# ArmDebuger_7-7_-CPLD.net
KiCad netlist of a schematic drawn in Altium Designer
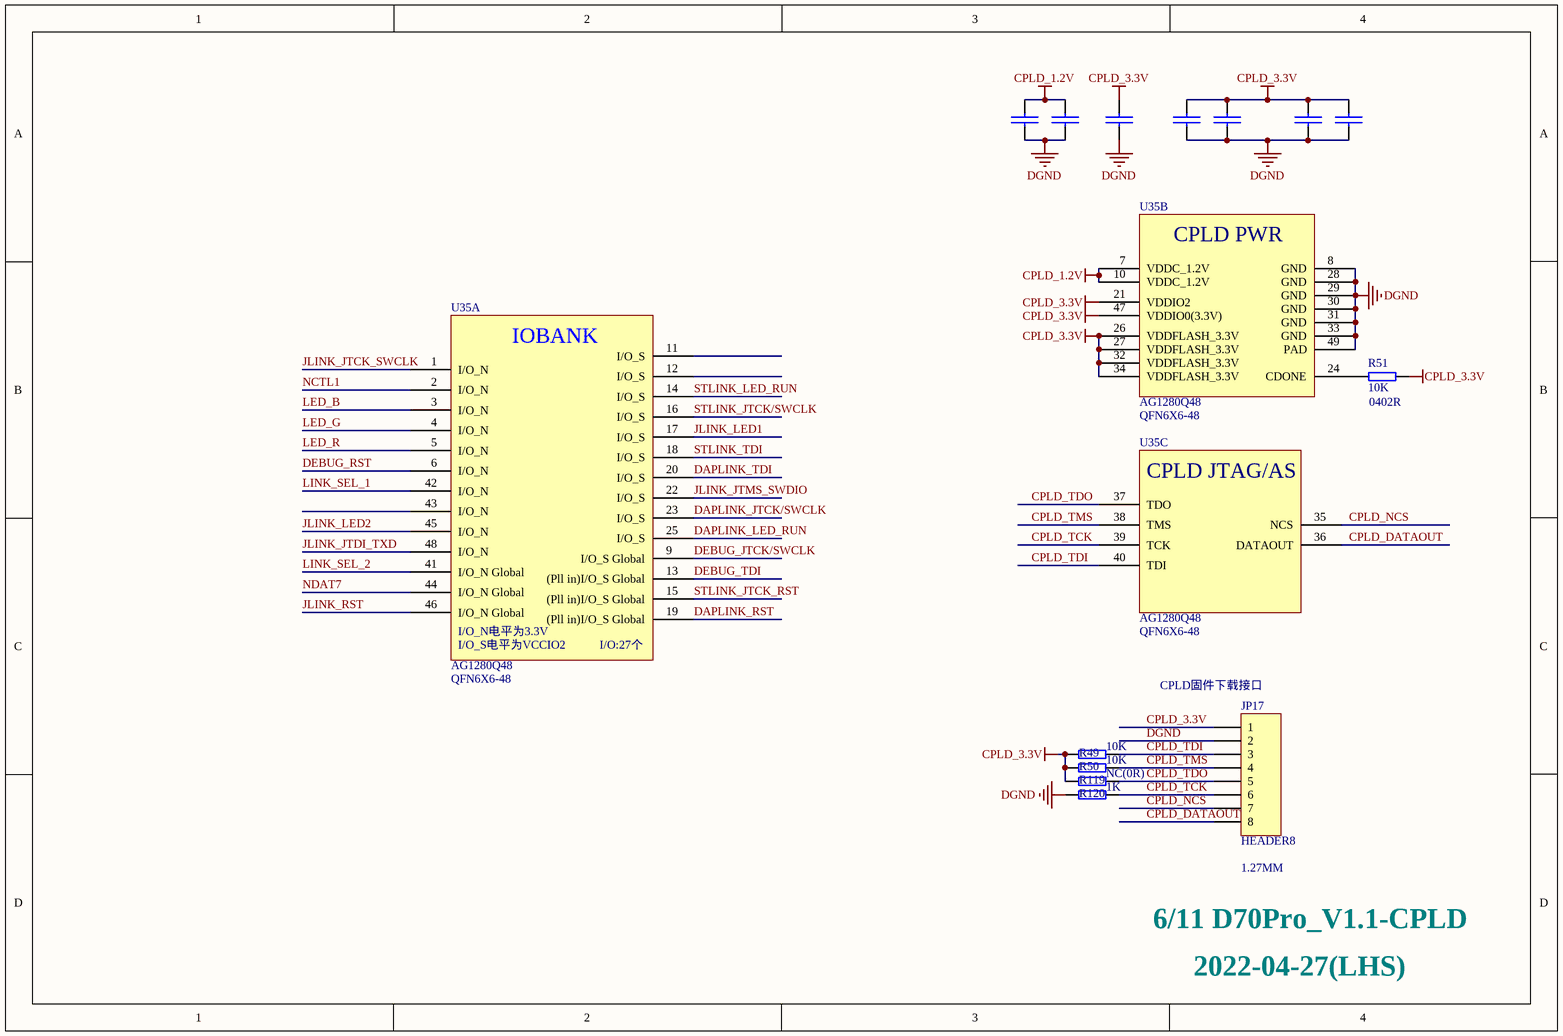
[diagram p0: ArmDebuger(7-7)-CPLD.SchDoc]

(export (version "E")
  (design (tool "Eeschema 10.0.6"))
  (components
    (comp (ref "C105") (value "104/X7R/16V") (footprint "0402C-SMD-M") (libsource (lib "*") (part "CAP")))
    (comp (ref "C172") (value "104/X7R/16V") (footprint "0402C-SMD-M") (libsource (lib "*") (part "CAP")))
    (comp (ref "C223") (value "104/X7R/16V") (footprint "0402C-SMD-M") (libsource (lib "*") (part "CAP")))
    (comp (ref "C224") (value "104/X7R/16V") (footprint "0402C-SMD-M") (libsource (lib "*") (part "CAP")))
    (comp (ref "C227") (value "104/X7R/16V") (footprint "0402C-SMD-M") (libsource (lib "*") (part "CAP")))
    (comp (ref "C228") (value "104/X7R/16V") (footprint "0402C-SMD-M") (libsource (lib "*") (part "CAP")))
    (comp (ref "C229") (value "104/X7R/16V") (footprint "0402C-SMD-M") (libsource (lib "*") (part "CAP")))
    (comp (ref "JP17")
      (value "HEADER8")
      (footprint "HEADER4x2-1.27mm")
      (fields (field (name "FP") "1.27MM"))
      (libsource (lib "conm") (part "HEADER8"))
    )
    (comp (ref "R49")
      (value "10K")
      (footprint "0402R-SMD-M")
      (libsource (lib "altium-import") (part "root_2_RES_"))
    )
    (comp (ref "R50")
      (value "10K")
      (footprint "0402R-SMD-M")
      (libsource (lib "altium-import") (part "root_2_RES_"))
    )
    (comp (ref "R51")
      (value "10K")
      (footprint "0402R-SMD-M")
      (fields (field (name "FP") "0402R"))
      (libsource (lib "altium-import") (part "root_2_RES_"))
    )
    (comp (ref "R119")
      (value "NC(0R)")
      (footprint "0402R-SMD-M")
      (libsource (lib "altium-import") (part "root_2_RES_"))
    )
    (comp (ref "R120")
      (value "1K")
      (footprint "0402R-SMD-M")
      (libsource (lib "altium-import") (part "root_2_RES_"))
    )
    (comp (ref "U35")
      (value "AG1280Q48")
      (footprint "QFN6X6-48")
      (fields (field (name "FP") "QFN6X6-48"))
      (libsource (lib "ic") (part "AG1280Q48"))
    )
  )
  (nets
    (net (code "1") (name "/CPLD_DATAOUT") (class "Default")
      (node (ref "JP17") (pin "8") (pinfunction "8_8") (pintype "passive"))
      (node (ref "U35") (pin "36") (pinfunction "DATAOUT_36") (pintype "passive"))
    )
    (net (code "2") (name "/CPLD_NCS") (class "Default")
      (node (ref "JP17") (pin "7") (pinfunction "7_7") (pintype "passive"))
      (node (ref "U35") (pin "35") (pinfunction "NCS_35") (pintype "passive"))
    )
    (net (code "3") (name "/CPLD_TCK") (class "Default")
      (node (ref "JP17") (pin "6") (pinfunction "6_6") (pintype "passive"))
      (node (ref "R120") (pin "1") (pinfunction "1_1") (pintype "passive"))
      (node (ref "U35") (pin "39") (pinfunction "TCK_39") (pintype "passive"))
    )
    (net (code "4") (name "/CPLD_TDI") (class "Default")
      (node (ref "JP17") (pin "3") (pinfunction "3_3") (pintype "passive"))
      (node (ref "R49") (pin "1") (pinfunction "1_1") (pintype "passive"))
      (node (ref "U35") (pin "40") (pinfunction "TDI_40") (pintype "passive"))
    )
    (net (code "5") (name "/CPLD_TDO") (class "Default")
      (node (ref "JP17") (pin "5") (pinfunction "5_5") (pintype "passive"))
      (node (ref "R119") (pin "1") (pinfunction "1_1") (pintype "passive"))
      (node (ref "U35") (pin "37") (pinfunction "TDO_37") (pintype "passive"))
    )
    (net (code "6") (name "/CPLD_TMS") (class "Default")
      (node (ref "JP17") (pin "4") (pinfunction "4_4") (pintype "passive"))
      (node (ref "R50") (pin "1") (pinfunction "1_1") (pintype "passive"))
      (node (ref "U35") (pin "38") (pinfunction "TMS_38") (pintype "passive"))
    )
    (net (code "7") (name "/DAPLINK_JTCK{slash}SWCLK") (class "Default")
      (node (ref "U35") (pin "23") (pinfunction "I/O_S_23") (pintype "passive"))
    )
    (net (code "8") (name "/DAPLINK_LED_RUN") (class "Default")
      (node (ref "U35") (pin "25") (pinfunction "I/O_S_25") (pintype "passive"))
    )
    (net (code "9") (name "/DAPLINK_RST") (class "Default")
      (node (ref "U35") (pin "19") (pinfunction "(Pll_in)I/O_S_Global_19") (pintype "passive"))
    )
    (net (code "10") (name "/DAPLINK_TDI") (class "Default")
      (node (ref "U35") (pin "20") (pinfunction "I/O_S_20") (pintype "passive"))
    )
    (net (code "11") (name "/DEBUG_JTCK{slash}SWCLK") (class "Default")
      (node (ref "U35") (pin "9") (pinfunction "I/O_S_Global_9") (pintype "passive"))
    )
    (net (code "12") (name "/DEBUG_RST") (class "Default")
      (node (ref "U35") (pin "6") (pinfunction "I/O_N_6") (pintype "passive"))
    )
    (net (code "13") (name "/DEBUG_TDI") (class "Default")
      (node (ref "U35") (pin "13") (pinfunction "(Pll_in)I/O_S_Global_13") (pintype "passive"))
    )
    (net (code "14") (name "/JLINK_JTCK_SWCLK") (class "Default")
      (node (ref "U35") (pin "1") (pinfunction "I/O_N_1") (pintype "passive"))
    )
    (net (code "15") (name "/JLINK_JTDI_TXD") (class "Default")
      (node (ref "U35") (pin "48") (pinfunction "I/O_N_48") (pintype "passive"))
    )
    (net (code "16") (name "/JLINK_JTMS_SWDIO") (class "Default")
      (node (ref "U35") (pin "22") (pinfunction "I/O_S_22") (pintype "passive"))
    )
    (net (code "17") (name "/JLINK_LED1") (class "Default")
      (node (ref "U35") (pin "17") (pinfunction "I/O_S_17") (pintype "passive"))
    )
    (net (code "18") (name "/JLINK_LED2") (class "Default")
      (node (ref "U35") (pin "45") (pinfunction "I/O_N_45") (pintype "passive"))
    )
    (net (code "19") (name "/JLINK_RST") (class "Default")
      (node (ref "U35") (pin "46") (pinfunction "I/O_N_Global_46") (pintype "passive"))
    )
    (net (code "20") (name "/LED_B") (class "Default")
      (node (ref "U35") (pin "3") (pinfunction "I/O_N_3") (pintype "passive"))
    )
    (net (code "21") (name "/LED_G") (class "Default")
      (node (ref "U35") (pin "4") (pinfunction "I/O_N_4") (pintype "passive"))
    )
    (net (code "22") (name "/LED_R") (class "Default")
      (node (ref "U35") (pin "5") (pinfunction "I/O_N_5") (pintype "passive"))
    )
    (net (code "23") (name "/LINK_SEL_1") (class "Default")
      (node (ref "U35") (pin "42") (pinfunction "I/O_N_42") (pintype "passive"))
    )
    (net (code "24") (name "/LINK_SEL_2") (class "Default")
      (node (ref "U35") (pin "41") (pinfunction "I/O_N_Global_41") (pintype "passive"))
    )
    (net (code "25") (name "/NCTL1") (class "Default")
      (node (ref "U35") (pin "2") (pinfunction "I/O_N_2") (pintype "passive"))
    )
    (net (code "26") (name "/NDAT7") (class "Default")
      (node (ref "U35") (pin "44") (pinfunction "I/O_N_Global_44") (pintype "passive"))
    )
    (net (code "27") (name "/STLINK_JTCK_RST") (class "Default")
      (node (ref "U35") (pin "15") (pinfunction "(Pll_in)I/O_S_Global_15") (pintype "passive"))
    )
    (net (code "28") (name "/STLINK_JTCK{slash}SWCLK") (class "Default")
      (node (ref "U35") (pin "16") (pinfunction "I/O_S_16") (pintype "passive"))
    )
    (net (code "29") (name "/STLINK_LED_RUN") (class "Default")
      (node (ref "U35") (pin "14") (pinfunction "I/O_S_14") (pintype "passive"))
    )
    (net (code "30") (name "/STLINK_TDI") (class "Default")
      (node (ref "U35") (pin "18") (pinfunction "I/O_S_18") (pintype "passive"))
    )
    (net (code "31") (name "CPLD_1.2V") (class "Default")
      (node (ref "C105") (pin "2") (pinfunction "1_2") (pintype "passive"))
      (node (ref "C229") (pin "1") (pinfunction "1_1") (pintype "passive"))
      (node (ref "U35") (pin "10") (pinfunction "VDDC_1.2V_10") (pintype "passive"))
      (node (ref "U35") (pin "7") (pinfunction "VDDC_1.2V_7") (pintype "passive"))
    )
    (net (code "32") (name "CPLD_3.3V") (class "Default")
      (node (ref "C172") (pin "2") (pinfunction "1_2") (pintype "passive"))
      (node (ref "C223") (pin "2") (pinfunction "1_2") (pintype "passive"))
      (node (ref "C224") (pin "2") (pinfunction "1_2") (pintype "passive"))
      (node (ref "C227") (pin "2") (pinfunction "1_2") (pintype "passive"))
      (node (ref "C228") (pin "2") (pinfunction "1_2") (pintype "passive"))
      (node (ref "JP17") (pin "1") (pinfunction "1_1") (pintype "passive"))
      (node (ref "R119") (pin "2") (pinfunction "2_2") (pintype "passive"))
      (node (ref "R49") (pin "2") (pinfunction "2_2") (pintype "passive"))
      (node (ref "R50") (pin "2") (pinfunction "2_2") (pintype "passive"))
      (node (ref "R51") (pin "1") (pinfunction "1_1") (pintype "passive"))
      (node (ref "U35") (pin "21") (pinfunction "VDDIO2_21") (pintype "passive"))
      (node (ref "U35") (pin "26") (pinfunction "VDDFLASH_3.3V_26") (pintype "passive"))
      (node (ref "U35") (pin "27") (pinfunction "VDDFLASH_3.3V_27") (pintype "passive"))
      (node (ref "U35") (pin "32") (pinfunction "VDDFLASH_3.3V_32") (pintype "passive"))
      (node (ref "U35") (pin "34") (pinfunction "VDDFLASH_3.3V_34") (pintype "passive"))
      (node (ref "U35") (pin "47") (pinfunction "VDDIO0(3.3V)_47") (pintype "passive"))
    )
    (net (code "33") (name "DGND") (class "Default")
      (node (ref "C105") (pin "1") (pinfunction "1_1") (pintype "passive"))
      (node (ref "C172") (pin "1") (pinfunction "1_1") (pintype "passive"))
      (node (ref "C223") (pin "1") (pinfunction "1_1") (pintype "passive"))
      (node (ref "C224") (pin "1") (pinfunction "1_1") (pintype "passive"))
      (node (ref "C227") (pin "1") (pinfunction "1_1") (pintype "passive"))
      (node (ref "C228") (pin "1") (pinfunction "1_1") (pintype "passive"))
      (node (ref "C229") (pin "2") (pinfunction "1_2") (pintype "passive"))
      (node (ref "JP17") (pin "2") (pinfunction "2_2") (pintype "passive"))
      (node (ref "R120") (pin "2") (pinfunction "2_2") (pintype "passive"))
      (node (ref "U35") (pin "28") (pinfunction "GND_28") (pintype "passive"))
      (node (ref "U35") (pin "29") (pinfunction "GND_29") (pintype "passive"))
      (node (ref "U35") (pin "30") (pinfunction "GND_30") (pintype "passive"))
      (node (ref "U35") (pin "31") (pinfunction "GND_31") (pintype "passive"))
      (node (ref "U35") (pin "33") (pinfunction "GND_33") (pintype "passive"))
      (node (ref "U35") (pin "49") (pinfunction "PAD_49") (pintype "passive"))
      (node (ref "U35") (pin "8") (pinfunction "GND_8") (pintype "passive"))
    )
    (net (code "34") (name "Net-(U35B-CDONE)") (class "Default")
      (node (ref "R51") (pin "2") (pinfunction "2_2") (pintype "passive"))
      (node (ref "U35") (pin "24") (pinfunction "CDONE_24") (pintype "passive"))
    )
    (net (code "35") (name "unconnected-(U35A-I{slash}O_N-Pad43)") (class "Default")
      (node (ref "U35") (pin "43") (pinfunction "I/O_N_43") (pintype "passive"))
    )
    (net (code "36") (name "unconnected-(U35A-I{slash}O_S-Pad11)") (class "Default")
      (node (ref "U35") (pin "11") (pinfunction "I/O_S_11") (pintype "passive"))
    )
    (net (code "37") (name "unconnected-(U35A-I{slash}O_S-Pad12)") (class "Default")
      (node (ref "U35") (pin "12") (pinfunction "I/O_S_12") (pintype "passive"))
    )
  )
)
